# Power_Board_Schematic_-_Backup.net
KiCad netlist of a schematic drawn in Altium Designer
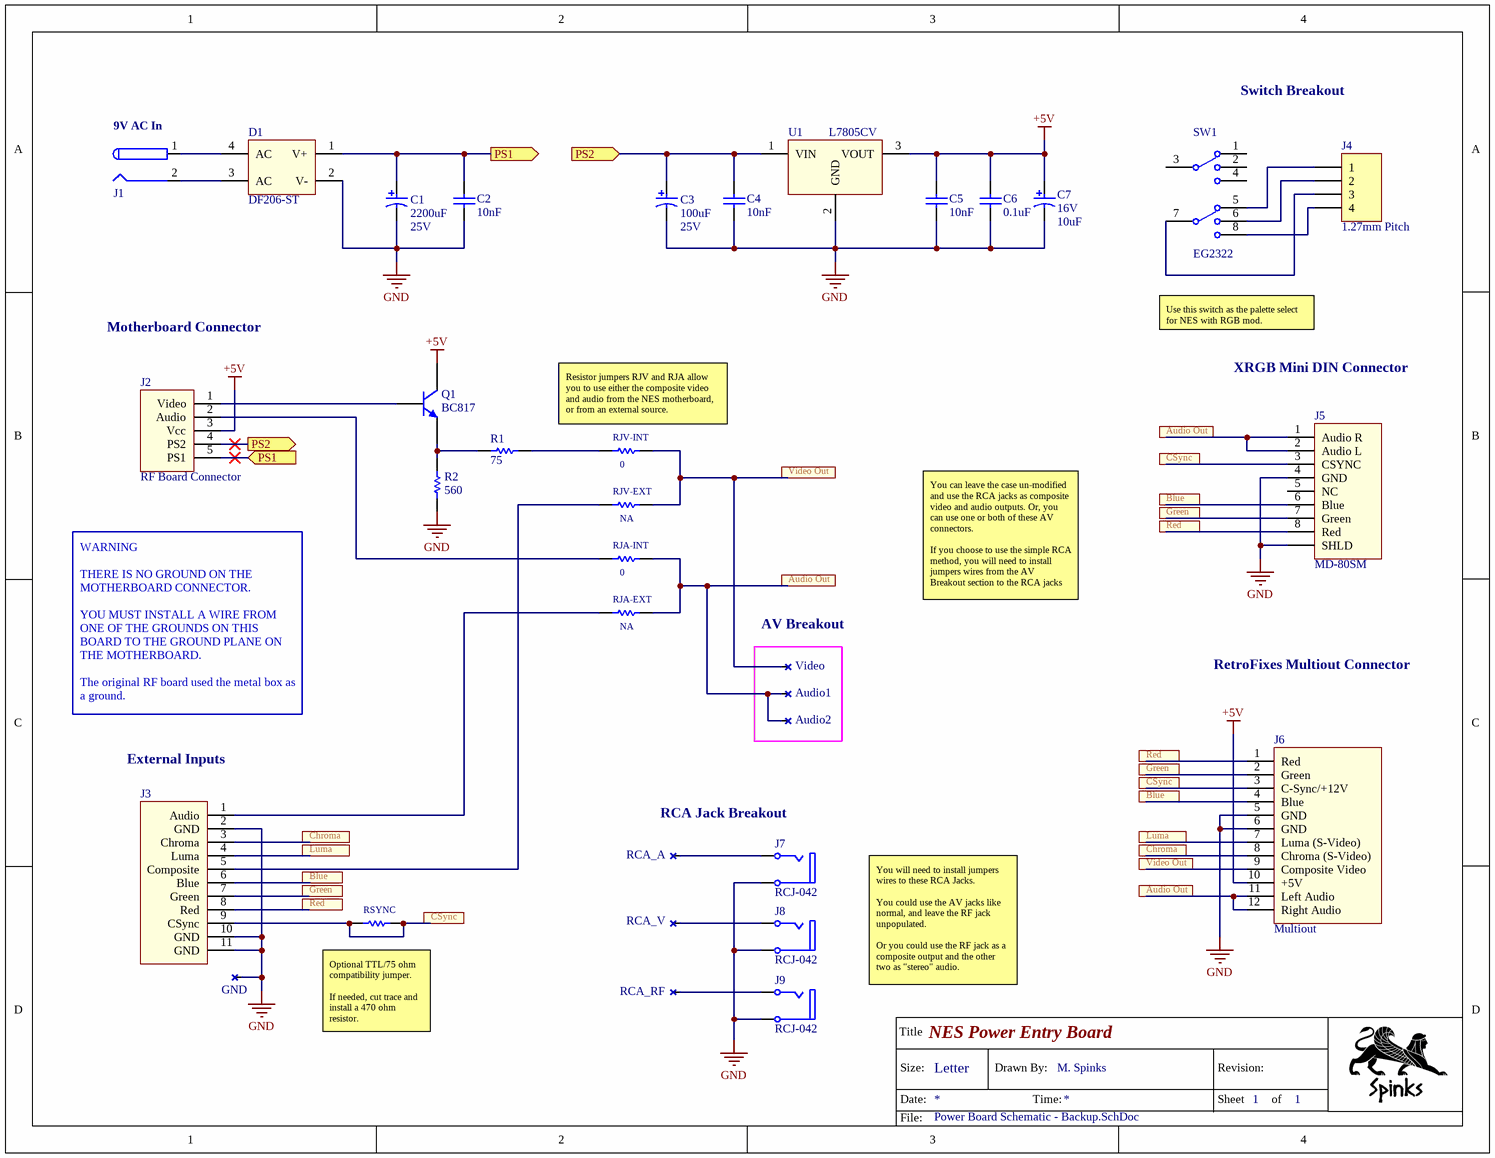
[diagram p0: Power Board Schematic - Backup.SchDoc]

(export (version "E")
  (design (tool "Eeschema 10.0.6"))
  (components
    (comp (ref "Audio1")
      (value "Wire Pad")
      (footprint "WIREPAD-09-15")
      (description "Wire Pad, 1 Pin, Through Hole, Vertical")
      (libsource (lib "Connectors") (part "-Wire Pad"))
    )
    (comp (ref "Audio2")
      (value "Wire Pad")
      (footprint "WIREPAD-09-15")
      (description "Wire Pad, 1 Pin, Through Hole, Vertical")
      (libsource (lib "Connectors") (part "-Wire Pad"))
    )
    (comp (ref "C1")
      (value "2200uF")
      (footprint "TH CAP-12.5X25MM-A1K2")
      (description "CAP, ALUM, TH, 12.5x25mm, 2200uF, 25V, 20%, Pitch 5.0mm")
      (fields
        (field (name "VOLTAGE") "25V")
        (field (name "REFERENCEPART") "ECA-1EHG222")
        (field (name "Comment") "Cap Aluminum")
      )
      (libsource (lib "Passive Components") (part "TH-ALUM-8-22-25V (ECA-1EHG222)"))
    )
    (comp (ref "C2")
      (value "10nF")
      (footprint "CAP 0805_N")
      (description "CAP, CER, 0805, 10nF, 50V, X7R, 10%")
      (fields (field (name "VOLTAGE") "50V") (field (name "REFERENCEPART") "VJ0603Y103KXACW1BC"))
      (libsource (lib "Passive Components") (part "0603-X7R-3-10-50V"))
    )
    (comp (ref "C3")
      (value "100uF")
      (footprint "TH CAP-6.3X11MM-A1K2")
      (description "CAP, ALUM, TH, 6.3x11mm, 100uF, 25V, 20%, Pitch 2.5mm")
      (fields
        (field (name "VOLTAGE") "25V")
        (field (name "REFERENCEPART") "ECA-1EM101")
        (field (name "Comment") "Cap Aluminum")
      )
      (libsource (lib "Passive Components") (part "TH-ALUM-7-10-25V (ECA-1EM101)"))
    )
    (comp (ref "C4")
      (value "10nF")
      (footprint "CAP 0805_N")
      (description "CAP, CER, 0805, 10nF, 50V, X7R, 10%")
      (fields (field (name "VOLTAGE") "50V") (field (name "REFERENCEPART") "VJ0603Y103KXACW1BC"))
      (libsource (lib "Passive Components") (part "0603-X7R-3-10-50V"))
    )
    (comp (ref "C5")
      (value "10nF")
      (footprint "CAP 0805_N")
      (description "CAP, CER, 0805, 10nF, 50V, X7R, 10%")
      (fields (field (name "VOLTAGE") "50V") (field (name "REFERENCEPART") "VJ0603Y103KXACW1BC"))
      (libsource (lib "Passive Components") (part "0603-X7R-3-10-50V"))
    )
    (comp (ref "C6")
      (value "0.1uF")
      (footprint "CAP 0805_N")
      (description "CAP, CER, 0805, 0.1uF, 50V, X7R, 10%")
      (fields (field (name "VOLTAGE") "50V") (field (name "REFERENCEPART") "VJ0805Y104KXXCW1BC"))
      (libsource (lib "Passive Components") (part "0805-X7R-4-10-50V"))
    )
    (comp (ref "C7")
      (value "10uF")
      (footprint "CAP EIA-A (3216) A1K2")
      (description "CAP, TANT,  1206, 10uF, 16V, 10%")
      (fields (field (name "VOLTAGE") "16V") (field (name "Comment") "Cap Tantalum"))
      (libsource (lib "Passive Components") (part "1206-TANT-6-10-16V (TAJA106K016RNJ)"))
    )
    (comp (ref "D1")
      (value "DF206-ST")
      (footprint "DFS4")
      (description "Full Wave Diode Bridge")
      (libsource (lib "Semiconductors") (part "Bridge (DF206-ST)"))
    )
    (comp (ref "GND")
      (value "Wire Pad")
      (footprint "WIREPAD-09-15")
      (description "Wire Pad, 1 Pin, Through Hole, Vertical")
      (libsource (lib "Connectors") (part "-Wire Pad"))
    )
    (comp (ref "J1")
      (value "PJ-037A")
      (footprint "PWR-JCK-ALT (PJ-037A/B)")
      (description "2.1mm ID, DC Power Supply Connector, 2 Pin")
      (libsource (lib "Connectors") (part "PWR-JCK (PJ-037A)"))
    )
    (comp (ref "J2")
      (value "RF Board Connector")
      (footprint "RF Board Connector")
      (description "Motherboard Connector to RF/Power Module")
      (libsource (lib "Specialty Components") (part "RF Board Connector"))
    )
    (comp (ref "J3")
      (value "1.27mm Pitch")
      (footprint "RF Board Mod Inputs")
      (description "Video and audio inputs for the RF Board Mod")
      (libsource (lib "Specialty Components") (part "RF Board Mod Input Header"))
    )
    (comp (ref "J4")
      (value "Header 1x4 1.27mm")
      (footprint "HDR1X4-127MM VERT - L")
      (description "Header, 4 Pin, 1.27mm Pitch, Vertical")
      (fields (field (name "LABEL") "1.27mm Pitch"))
      (libsource (lib "Connectors") (part "Header 1x4 - 1.27mm Vert"))
    )
    (comp (ref "J5")
      (value "MD-80SM")
      (footprint "MINI-DIN-8-ALT (MD-80SM)")
      (description "8 Pin Mini DIN Connector, Shielded, Through Hole, Right Angle")
      (libsource (lib "Connectors") (part "Mini-XRGB (MD-80SM)"))
    )
    (comp (ref "J6")
      (value "Multiout")
      (footprint "Multiout-2")
      (description "SNES Multiout Connector")
      (libsource (lib "Specialty Components") (part "Multiout Connector"))
    )
    (comp (ref "J7")
      (value "RCJ-042")
      (footprint "RCA-JCK-1 (RCJ-042-ALT1)")
      (description "RCA Phono Jack, Right Angle")
      (libsource (lib "Connectors") (part "RCA-JCK-1 (RCJ-042)"))
    )
    (comp (ref "J8")
      (value "RCJ-042")
      (footprint "RCA-JCK-1 (RCJ-042-ALT1)")
      (description "RCA Phono Jack, Right Angle")
      (libsource (lib "Connectors") (part "RCA-JCK-1 (RCJ-042)"))
    )
    (comp (ref "J9")
      (value "RCJ-042")
      (footprint "RCA-JCK-1 (RCJ-042-ALT1)")
      (description "RCA Phono Jack, Right Angle")
      (libsource (lib "Connectors") (part "RCA-JCK-1 (RCJ-042)"))
    )
    (comp (ref "Q1")
      (value "BC817")
      (footprint "SOT23-3")
      (description "General Purpose Transistor, NPN, 3-Pin, B1E2C3")
      (fields (field (name "Comment") "Transistor NPN"))
      (libsource (lib "Semiconductors") (part "BC817 NPN"))
    )
    (comp (ref "R1")
      (value "75")
      (footprint "RES 0805_N")
      (description "RES, SMD")
      (fields (field (name "Comment") "Resistor"))
      (libsource (lib "Passive Components") (part "-Resistor"))
    )
    (comp (ref "R2")
      (value "560")
      (footprint "RES 0805_N")
      (description "RES, SMD")
      (fields (field (name "Comment") "Resistor"))
      (libsource (lib "Passive Components") (part "-Resistor"))
    )
    (comp (ref "RCA_A")
      (value "Wire Pad")
      (footprint "WIREPAD-09-15")
      (description "Wire Pad, 1 Pin, Through Hole, Vertical")
      (libsource (lib "Connectors") (part "-Wire Pad"))
    )
    (comp (ref "RCA_RF")
      (value "Wire Pad")
      (footprint "WIREPAD-09-15")
      (description "Wire Pad, 1 Pin, Through Hole, Vertical")
      (libsource (lib "Connectors") (part "-Wire Pad"))
    )
    (comp (ref "RCA_V")
      (value "Wire Pad")
      (footprint "WIREPAD-09-15")
      (description "Wire Pad, 1 Pin, Through Hole, Vertical")
      (libsource (lib "Connectors") (part "-Wire Pad"))
    )
    (comp (ref "RJA-EXT")
      (value "NA")
      (footprint "RES 0805_N")
      (description "RES, SMD")
      (fields (field (name "Comment") "Resistor"))
      (libsource (lib "Passive Components") (part "-Resistor"))
    )
    (comp (ref "RJA-INT")
      (value "0")
      (footprint "RES 0805_N")
      (description "RES, SMD")
      (fields (field (name "Comment") "Resistor"))
      (libsource (lib "Passive Components") (part "-Resistor"))
    )
    (comp (ref "RJV-EXT")
      (value "NA")
      (footprint "RES 0805_N")
      (description "RES, SMD")
      (fields (field (name "Comment") "Resistor"))
      (libsource (lib "Passive Components") (part "-Resistor"))
    )
    (comp (ref "RJV-INT")
      (value "0")
      (footprint "RES 0805_N")
      (description "RES, SMD")
      (fields (field (name "Comment") "Resistor"))
      (libsource (lib "Passive Components") (part "-Resistor"))
    )
    (comp (ref "RSYNC")
      (value "Resistor")
      (footprint "RES 0805_N")
      (description "RES, SMD")
      (libsource (lib "Passive Components") (part "-Resistor"))
    )
    (comp (ref "SW1")
      (value "EG2322")
      (footprint "SW-DP3T (EG2322)")
      (description "Dual Pole, Three Throw")
      (fields (field (name "Comment") "DP3T"))
      (libsource (lib "Electromechanical") (part "SW-DP3T (EG2322)"))
    )
    (comp (ref "U1")
      (value "L7805CV")
      (footprint "TO-220AB")
      (description "Fixed 5V Regulator, 1.5A, Through Hole")
      (libsource (lib "Integrated Circuits") (part "L7805CV"))
    )
    (comp (ref "Video")
      (value "Wire Pad")
      (footprint "WIREPAD-09-15")
      (description "Wire Pad, 1 Pin, Through Hole, Vertical")
      (libsource (lib "Connectors") (part "-Wire Pad"))
    )
  )
  (nets
    (net (code "1") (name "+5V") (class "Default")
      (node (ref "C5") (pin "2") (pinfunction "2_2") (pintype "passive"))
      (node (ref "C6") (pin "2") (pinfunction "2_2") (pintype "passive"))
      (node (ref "C7") (pin "1") (pinfunction "A_1") (pintype "passive"))
      (node (ref "J2") (pin "3") (pinfunction "Vcc_3") (pintype "passive"))
      (node (ref "J6") (pin "10") (pinfunction "+5V_10") (pintype "passive"))
      (node (ref "Q1") (pin "3") (pinfunction "C_3") (pintype "passive"))
      (node (ref "U1") (pin "3") (pinfunction "VOUT_3") (pintype "power_in"))
    )
    (net (code "2") (name "/Audio Out") (class "Default")
      (node (ref "Audio1") (pin "1") (pinfunction "1_1") (pintype "passive"))
      (node (ref "Audio2") (pin "1") (pinfunction "1_1") (pintype "passive"))
      (node (ref "J5") (pin "1") (pinfunction "Audio_R_1") (pintype "passive"))
      (node (ref "J5") (pin "2") (pinfunction "Audio_L_2") (pintype "passive"))
      (node (ref "J6") (pin "11") (pinfunction "Left_Audio_11") (pintype "passive"))
      (node (ref "J6") (pin "12") (pinfunction "Right_Audio_12") (pintype "passive"))
      (node (ref "RJA-EXT") (pin "1") (pinfunction "1_1") (pintype "passive"))
      (node (ref "RJA-INT") (pin "1") (pinfunction "1_1") (pintype "passive"))
    )
    (net (code "3") (name "/Blue") (class "Default")
      (node (ref "J3") (pin "6") (pinfunction "Blue_6") (pintype "passive"))
      (node (ref "J5") (pin "6") (pinfunction "Blue_6") (pintype "passive"))
      (node (ref "J6") (pin "4") (pinfunction "Blue_4") (pintype "passive"))
    )
    (net (code "4") (name "/CSync") (class "Default")
      (node (ref "J3") (pin "9") (pinfunction "CSync_9") (pintype "passive"))
      (node (ref "J5") (pin "3") (pinfunction "CSYNC_3") (pintype "passive"))
      (node (ref "J6") (pin "3") (pinfunction "C-Sync/+12V_3") (pintype "passive"))
      (node (ref "RSYNC") (pin "1") (pinfunction "1_1") (pintype "passive"))
      (node (ref "RSYNC") (pin "2") (pinfunction "2_2") (pintype "passive"))
    )
    (net (code "5") (name "/Chroma") (class "Default")
      (node (ref "J3") (pin "3") (pinfunction "Chroma_3") (pintype "passive"))
      (node (ref "J6") (pin "8") (pinfunction "Chroma_(S-Video)_8") (pintype "passive"))
    )
    (net (code "6") (name "/Green") (class "Default")
      (node (ref "J3") (pin "7") (pinfunction "Green_7") (pintype "passive"))
      (node (ref "J5") (pin "7") (pinfunction "Green_7") (pintype "passive"))
      (node (ref "J6") (pin "2") (pinfunction "Green_2") (pintype "passive"))
    )
    (net (code "7") (name "/Luma") (class "Default")
      (node (ref "J3") (pin "4") (pinfunction "Luma_4") (pintype "passive"))
      (node (ref "J6") (pin "7") (pinfunction "Luma_(S-Video)_7") (pintype "passive"))
    )
    (net (code "8") (name "/PS1") (class "Default")
      (node (ref "C1") (pin "1") (pinfunction "A_1") (pintype "passive"))
      (node (ref "C2") (pin "2") (pinfunction "2_2") (pintype "passive"))
      (node (ref "D1") (pin "1") (pinfunction "V+_1") (pintype "passive"))
      (node (ref "J2") (pin "5") (pinfunction "PS1_5") (pintype "passive"))
    )
    (net (code "9") (name "/PS2") (class "Default")
      (node (ref "C3") (pin "1") (pinfunction "A_1") (pintype "passive"))
      (node (ref "C4") (pin "2") (pinfunction "2_2") (pintype "passive"))
      (node (ref "J2") (pin "4") (pinfunction "PS2_4") (pintype "passive"))
      (node (ref "U1") (pin "1") (pinfunction "VIN_1") (pintype "power_in"))
    )
    (net (code "10") (name "/Red") (class "Default")
      (node (ref "J3") (pin "8") (pinfunction "Red_8") (pintype "passive"))
      (node (ref "J5") (pin "8") (pinfunction "Red_8") (pintype "passive"))
      (node (ref "J6") (pin "1") (pinfunction "Red_1") (pintype "passive"))
    )
    (net (code "11") (name "/Video Out") (class "Default")
      (node (ref "J6") (pin "9") (pinfunction "Composite_Video_9") (pintype "passive"))
      (node (ref "RJV-EXT") (pin "1") (pinfunction "1_1") (pintype "passive"))
      (node (ref "RJV-INT") (pin "1") (pinfunction "1_1") (pintype "passive"))
      (node (ref "Video") (pin "1") (pinfunction "1_1") (pintype "passive"))
    )
    (net (code "12") (name "GND") (class "Default")
      (node (ref "C1") (pin "2") (pinfunction "K_2") (pintype "passive"))
      (node (ref "C2") (pin "1") (pinfunction "1_1") (pintype "passive"))
      (node (ref "C3") (pin "2") (pinfunction "K_2") (pintype "passive"))
      (node (ref "C4") (pin "1") (pinfunction "1_1") (pintype "passive"))
      (node (ref "C5") (pin "1") (pinfunction "1_1") (pintype "passive"))
      (node (ref "C6") (pin "1") (pinfunction "1_1") (pintype "passive"))
      (node (ref "C7") (pin "2") (pinfunction "K_2") (pintype "passive"))
      (node (ref "D1") (pin "2") (pinfunction "V-_2") (pintype "passive"))
      (node (ref "GND") (pin "1") (pinfunction "1_1") (pintype "passive"))
      (node (ref "J3") (pin "10") (pinfunction "GND_10") (pintype "passive"))
      (node (ref "J3") (pin "11") (pinfunction "GND_11") (pintype "passive"))
      (node (ref "J3") (pin "2") (pinfunction "GND_2") (pintype "passive"))
      (node (ref "J5") (pin "4") (pinfunction "GND_4") (pintype "passive"))
      (node (ref "J5") (pin "SHLD") (pinfunction "SHLD_SHLD") (pintype "passive"))
      (node (ref "J6") (pin "5") (pinfunction "GND_5") (pintype "passive"))
      (node (ref "J6") (pin "6") (pinfunction "GND_6") (pintype "passive"))
      (node (ref "J7") (pin "2") (pinfunction "Sleeve_2") (pintype "passive"))
      (node (ref "J8") (pin "2") (pinfunction "Sleeve_2") (pintype "passive"))
      (node (ref "J9") (pin "2") (pinfunction "Sleeve_2") (pintype "passive"))
      (node (ref "R2") (pin "1") (pinfunction "1_1") (pintype "passive"))
      (node (ref "U1") (pin "2") (pinfunction "GND_2") (pintype "passive"))
    )
    (net (code "13") (name "Net-(D1-AC-Pad3)") (class "Default")
      (node (ref "D1") (pin "3") (pinfunction "AC_3") (pintype "passive"))
      (node (ref "J1") (pin "2") (pinfunction "2_2") (pintype "power_in"))
    )
    (net (code "14") (name "Net-(D1-AC-Pad4)") (class "Default")
      (node (ref "D1") (pin "4") (pinfunction "AC_4") (pintype "passive"))
      (node (ref "J1") (pin "1") (pinfunction "1_1") (pintype "power_in"))
    )
    (net (code "15") (name "Net-(J2-Audio)") (class "Default")
      (node (ref "J2") (pin "2") (pinfunction "Audio_2") (pintype "passive"))
      (node (ref "RJA-INT") (pin "2") (pinfunction "2_2") (pintype "passive"))
    )
    (net (code "16") (name "Net-(J2-Video)") (class "Default")
      (node (ref "J2") (pin "1") (pinfunction "Video_1") (pintype "passive"))
      (node (ref "Q1") (pin "1") (pinfunction "B_1") (pintype "passive"))
    )
    (net (code "17") (name "Net-(J3-Audio)") (class "Default")
      (node (ref "J3") (pin "1") (pinfunction "Audio_1") (pintype "passive"))
      (node (ref "RJA-EXT") (pin "2") (pinfunction "2_2") (pintype "passive"))
    )
    (net (code "18") (name "Net-(J3-Composite)") (class "Default")
      (node (ref "J3") (pin "5") (pinfunction "Composite_5") (pintype "passive"))
      (node (ref "RJV-EXT") (pin "2") (pinfunction "2_2") (pintype "passive"))
    )
    (net (code "19") (name "Net-(J4-Pad1)") (class "Default")
      (node (ref "J4") (pin "1") (pinfunction "1_1") (pintype "passive"))
      (node (ref "SW1") (pin "5") (pinfunction "5_5") (pintype "passive"))
    )
    (net (code "20") (name "Net-(J4-Pad2)") (class "Default")
      (node (ref "J4") (pin "2") (pinfunction "2_2") (pintype "passive"))
      (node (ref "SW1") (pin "6") (pinfunction "6_6") (pintype "passive"))
    )
    (net (code "21") (name "Net-(J4-Pad3)") (class "Default")
      (node (ref "J4") (pin "3") (pinfunction "3_3") (pintype "passive"))
      (node (ref "SW1") (pin "7") (pinfunction "7_7") (pintype "passive"))
    )
    (net (code "22") (name "Net-(J4-Pad4)") (class "Default")
      (node (ref "J4") (pin "4") (pinfunction "4_4") (pintype "passive"))
      (node (ref "SW1") (pin "8") (pinfunction "8_8") (pintype "passive"))
    )
    (net (code "23") (name "Net-(J7-Tip)") (class "Default")
      (node (ref "J7") (pin "1") (pinfunction "Tip_1") (pintype "passive"))
      (node (ref "RCA_A") (pin "1") (pinfunction "1_1") (pintype "passive"))
    )
    (net (code "24") (name "Net-(J8-Tip)") (class "Default")
      (node (ref "J8") (pin "1") (pinfunction "Tip_1") (pintype "passive"))
      (node (ref "RCA_V") (pin "1") (pinfunction "1_1") (pintype "passive"))
    )
    (net (code "25") (name "Net-(J9-Tip)") (class "Default")
      (node (ref "J9") (pin "1") (pinfunction "Tip_1") (pintype "passive"))
      (node (ref "RCA_RF") (pin "1") (pinfunction "1_1") (pintype "passive"))
    )
    (net (code "26") (name "Net-(Q1-E)") (class "Default")
      (node (ref "Q1") (pin "2") (pinfunction "E_2") (pintype "passive"))
      (node (ref "R1") (pin "2") (pinfunction "2_2") (pintype "passive"))
      (node (ref "R2") (pin "2") (pinfunction "2_2") (pintype "passive"))
    )
    (net (code "27") (name "Net-(R1-Pad1)") (class "Default")
      (node (ref "R1") (pin "1") (pinfunction "1_1") (pintype "passive"))
      (node (ref "RJV-INT") (pin "2") (pinfunction "2_2") (pintype "passive"))
    )
    (net (code "28") (name "unconnected-(J5-NC-Pad5)") (class "Default")
      (node (ref "J5") (pin "5") (pinfunction "NC_5") (pintype "passive"))
    )
    (net (code "29") (name "unconnected-(SW1-Pad1)") (class "Default")
      (node (ref "SW1") (pin "1") (pinfunction "1_1") (pintype "passive"))
    )
    (net (code "30") (name "unconnected-(SW1-Pad2)") (class "Default")
      (node (ref "SW1") (pin "2") (pinfunction "2_2") (pintype "passive"))
    )
    (net (code "31") (name "unconnected-(SW1-Pad3)") (class "Default")
      (node (ref "SW1") (pin "3") (pinfunction "3_3") (pintype "passive"))
    )
    (net (code "32") (name "unconnected-(SW1-Pad4)") (class "Default")
      (node (ref "SW1") (pin "4") (pinfunction "4_4") (pintype "passive"))
    )
  )
)
